# FluxamasynthFeather.net
KiCad netlist of a schematic drawn in EAGLE
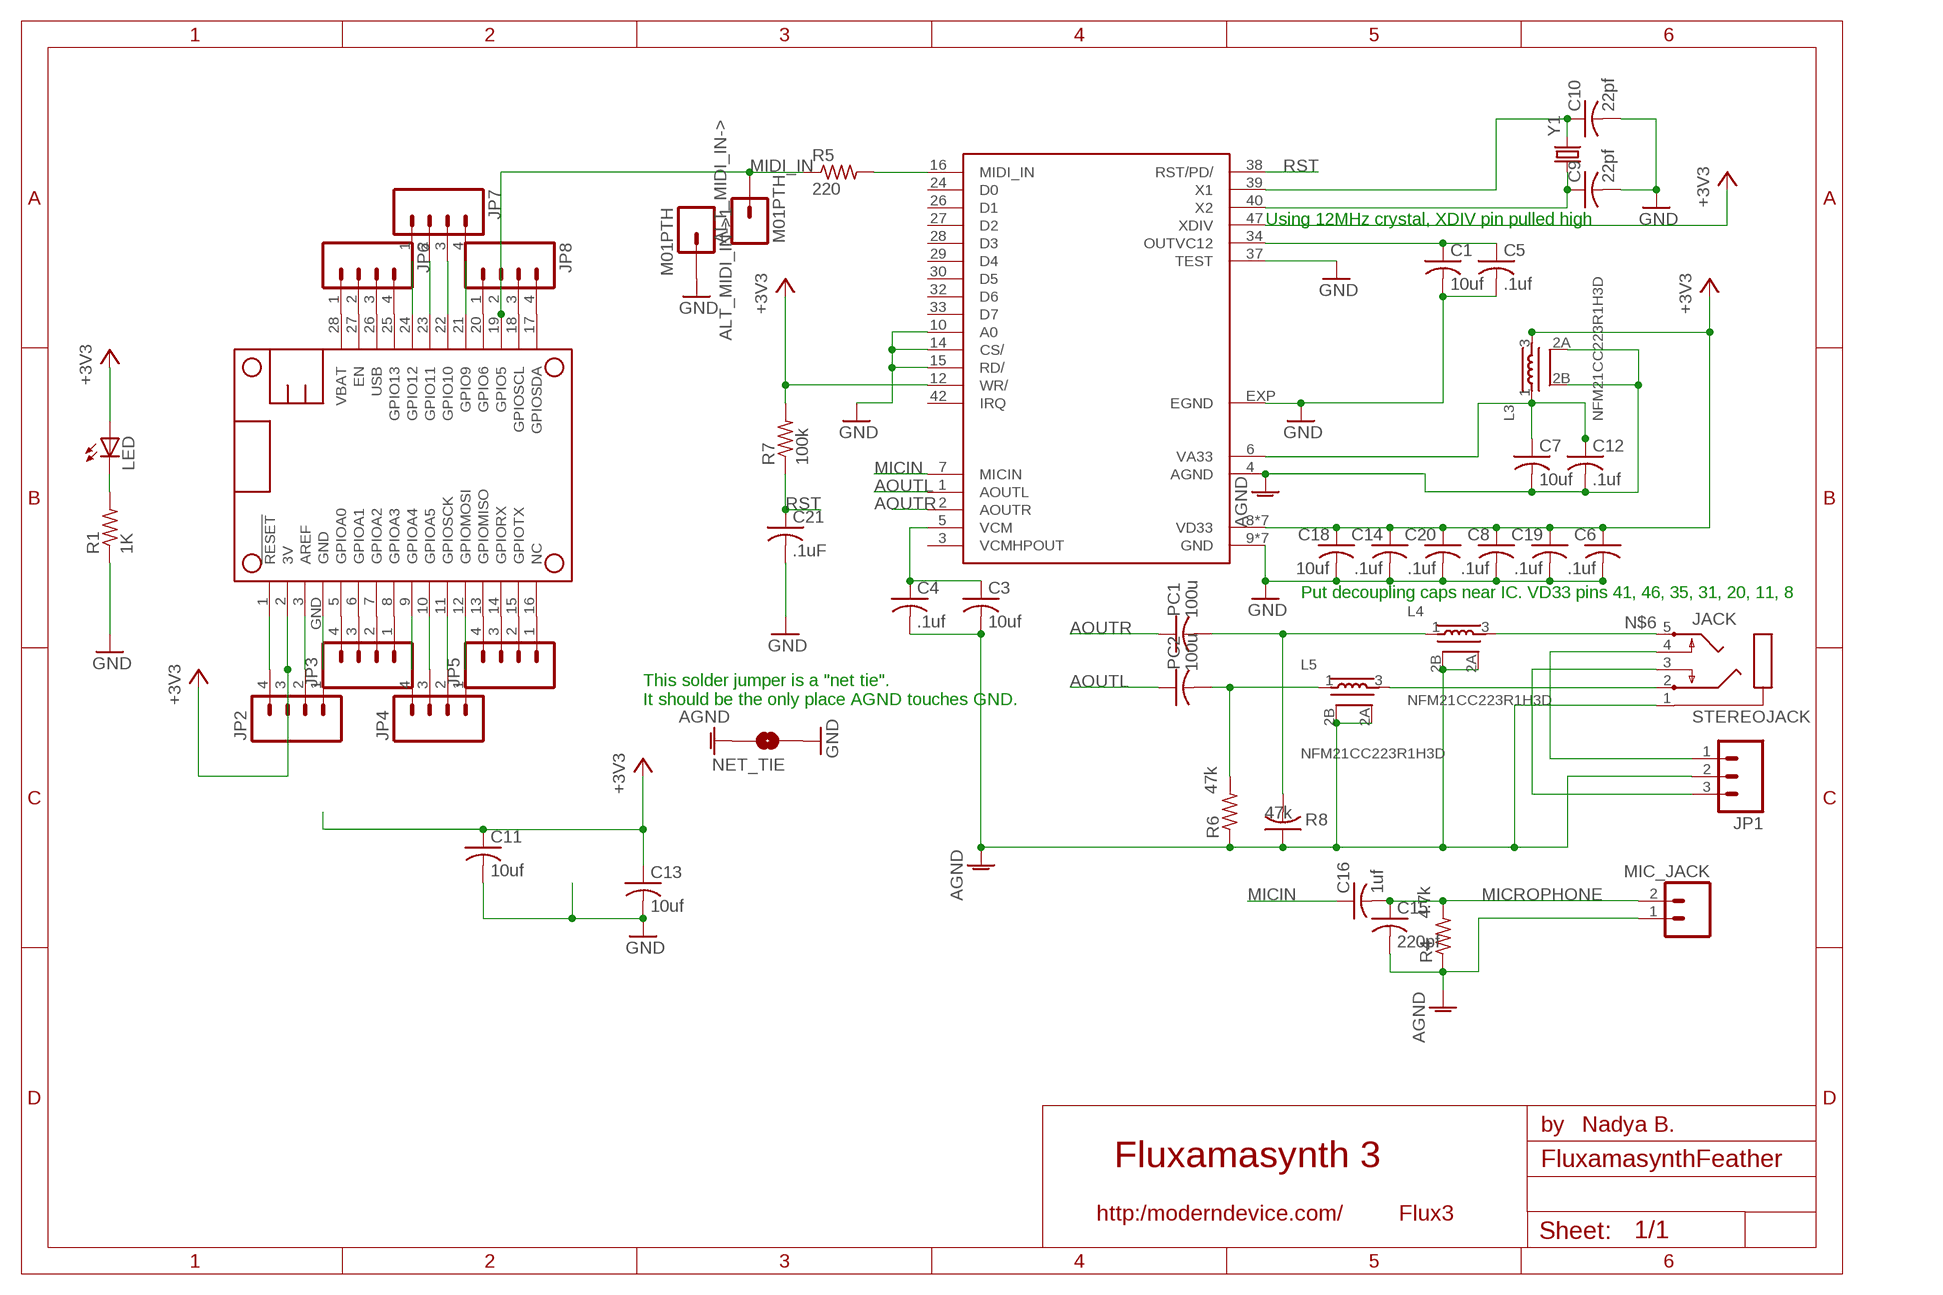
[diagram p0: schematic, sheet 1]

(export (version "E")
  (design (tool "Eeschema 10.0.6"))
  (components
    (comp (ref "ALT_MIDI_IN->")
      (value "M01PTH")
      (footprint "eagle-import:1X01")
      (libsource (lib "eagle-import") (part "M01PTH"))
    )
    (comp (ref "ALT_MIDI_IN->1")
      (value "M01PTH")
      (footprint "eagle-import:1X01")
      (libsource (lib "eagle-import") (part "M01PTH"))
    )
    (comp (ref "C1")
      (value "10uf")
      (footprint "eagle-import:C0805K")
      (libsource (lib "eagle-import") (part "C-USC0805K"))
    )
    (comp (ref "C3")
      (value "10uf")
      (footprint "eagle-import:C0805K")
      (libsource (lib "eagle-import") (part "C-USC0805K"))
    )
    (comp (ref "C4")
      (value ".1uf")
      (footprint "eagle-import:C0603K")
      (libsource (lib "eagle-import") (part "C-USC0603K"))
    )
    (comp (ref "C5")
      (value ".1uf")
      (footprint "eagle-import:C0603K")
      (libsource (lib "eagle-import") (part "C-USC0603K"))
    )
    (comp (ref "C6")
      (value ".1uf")
      (footprint "eagle-import:C0603K")
      (libsource (lib "eagle-import") (part "C-USC0603K"))
    )
    (comp (ref "C7")
      (value "10uf")
      (footprint "eagle-import:C0805K")
      (libsource (lib "eagle-import") (part "C-USC0805K"))
    )
    (comp (ref "C8")
      (value ".1uf")
      (footprint "eagle-import:C0603K")
      (libsource (lib "eagle-import") (part "C-USC0603K"))
    )
    (comp (ref "C9")
      (value "22pf")
      (footprint "eagle-import:C0603")
      (libsource (lib "eagle-import") (part "C-USC0603"))
    )
    (comp (ref "C10")
      (value "22pf")
      (footprint "eagle-import:C0603")
      (libsource (lib "eagle-import") (part "C-USC0603"))
    )
    (comp (ref "C11")
      (value "10uf")
      (footprint "eagle-import:C0805K")
      (libsource (lib "eagle-import") (part "C-USC0805K"))
    )
    (comp (ref "C12")
      (value ".1uf")
      (footprint "eagle-import:C0603K")
      (libsource (lib "eagle-import") (part "C-USC0603K"))
    )
    (comp (ref "C13")
      (value "10uf")
      (footprint "eagle-import:C0805K")
      (libsource (lib "eagle-import") (part "C-USC0805K"))
    )
    (comp (ref "C14")
      (value ".1uf")
      (footprint "eagle-import:C0603K")
      (libsource (lib "eagle-import") (part "C-USC0603K"))
    )
    (comp (ref "C15")
      (value "220pf")
      (footprint "eagle-import:C0805K")
      (libsource (lib "eagle-import") (part "C-USC0805K"))
    )
    (comp (ref "C16")
      (value "1uf")
      (footprint "eagle-import:C0603K")
      (libsource (lib "eagle-import") (part "C-USC0603K"))
    )
    (comp (ref "C18")
      (value "10uf")
      (footprint "eagle-import:C0603K")
      (libsource (lib "eagle-import") (part "C-USC0603K"))
    )
    (comp (ref "C19")
      (value ".1uf")
      (footprint "eagle-import:C0603K")
      (libsource (lib "eagle-import") (part "C-USC0603K"))
    )
    (comp (ref "C20")
      (value ".1uf")
      (footprint "eagle-import:C0603K")
      (libsource (lib "eagle-import") (part "C-USC0603K"))
    )
    (comp (ref "C21")
      (value ".1uF")
      (footprint "eagle-import:C0603K")
      (libsource (lib "eagle-import") (part "C-USC0603K"))
    )
    (comp (ref "JACK")
      (value "STEREOJACK")
      (footprint "eagle-import:STX3100")
      (libsource (lib "eagle-import") (part "STEREOJACK"))
    )
    (comp (ref "JP1")
      (value "M03PTH")
      (footprint "eagle-import:1X03")
      (libsource (lib "eagle-import") (part "M03PTH"))
    )
    (comp (ref "JP2")
      (value "M041X04_NO_SILK")
      (footprint "eagle-import:1X04_NO_SILK")
      (libsource (lib "eagle-import") (part "M041X04_NO_SILK"))
    )
    (comp (ref "JP3")
      (value "M041X04_NO_SILK")
      (footprint "eagle-import:1X04_NO_SILK")
      (libsource (lib "eagle-import") (part "M041X04_NO_SILK"))
    )
    (comp (ref "JP4")
      (value "M041X04_NO_SILK")
      (footprint "eagle-import:1X04_NO_SILK")
      (libsource (lib "eagle-import") (part "M041X04_NO_SILK"))
    )
    (comp (ref "JP5")
      (value "M041X04_NO_SILK")
      (footprint "eagle-import:1X04_NO_SILK")
      (libsource (lib "eagle-import") (part "M041X04_NO_SILK"))
    )
    (comp (ref "JP6")
      (value "M041X04_NO_SILK")
      (footprint "eagle-import:1X04_NO_SILK")
      (libsource (lib "eagle-import") (part "M041X04_NO_SILK"))
    )
    (comp (ref "JP7")
      (value "M041X04_NO_SILK")
      (footprint "eagle-import:1X04_NO_SILK")
      (libsource (lib "eagle-import") (part "M041X04_NO_SILK"))
    )
    (comp (ref "JP8")
      (value "M041X04_NO_SILK")
      (footprint "eagle-import:1X04_NO_SILK")
      (libsource (lib "eagle-import") (part "M041X04_NO_SILK"))
    )
    (comp (ref "L3")
      (value "NFM21CC223R1H3D")
      (footprint "eagle-import:3PC")
      (libsource (lib "eagle-import") (part "NFM21CC223R1H3D"))
    )
    (comp (ref "L4")
      (value "NFM21CC223R1H3D")
      (footprint "eagle-import:3PC")
      (libsource (lib "eagle-import") (part "NFM21CC223R1H3D"))
    )
    (comp (ref "L5")
      (value "NFM21CC223R1H3D")
      (footprint "eagle-import:3PC")
      (libsource (lib "eagle-import") (part "NFM21CC223R1H3D"))
    )
    (comp (ref "LED")
      (value "LED0603")
      (footprint "eagle-import:LED-0603")
      (libsource (lib "eagle-import") (part "LED0603"))
    )
    (comp (ref "MIC_JACK")
      (value "M02PTH")
      (footprint "eagle-import:1X02")
      (libsource (lib "eagle-import") (part "M02PTH"))
    )
    (comp (ref "MS1")
      (value "FEATHERWING")
      (footprint "eagle-import:FEATHERWING")
      (libsource (lib "eagle-import") (part "FEATHERWING"))
    )
    (comp (ref "NET_TIE")
      (value "MODERNDEVICE_SOLDERJUMPERTRACE")
      (footprint "eagle-import:MODERNDEVICE_SJ_2S-TRACE")
      (libsource (lib "eagle-import") (part "MODERNDEVICE_SOLDERJUMPERTRACE"))
    )
    (comp (ref "PC1")
      (value "100u")
      (footprint "eagle-import:C1206K")
      (libsource (lib "eagle-import") (part "C-USC1206K"))
    )
    (comp (ref "PC2")
      (value "100u")
      (footprint "eagle-import:C1206K")
      (libsource (lib "eagle-import") (part "C-USC1206K"))
    )
    (comp (ref "R1")
      (value "1K")
      (footprint "eagle-import:R0603")
      (libsource (lib "eagle-import") (part "R-US_R0603"))
    )
    (comp (ref "R4")
      (value "4.7k")
      (footprint "eagle-import:R0603")
      (libsource (lib "eagle-import") (part "R-US_R0603"))
    )
    (comp (ref "R5")
      (value "220")
      (footprint "eagle-import:R0603")
      (libsource (lib "eagle-import") (part "R-US_R0603"))
    )
    (comp (ref "R6")
      (value "47k")
      (footprint "eagle-import:R0603")
      (libsource (lib "eagle-import") (part "R-US_R0603"))
    )
    (comp (ref "R7")
      (value "100k")
      (footprint "eagle-import:R0603")
      (libsource (lib "eagle-import") (part "R-US_R0603"))
    )
    (comp (ref "R8")
      (value "47k")
      (footprint "eagle-import:C0603K")
      (libsource (lib "eagle-import") (part "C-USC0603K"))
    )
    (comp (ref "SAM2695")
      (value "SAM2695")
      (footprint "eagle-import:QFN48")
      (libsource (lib "eagle-import") (part "SAM2695"))
    )
    (comp (ref "Y1")
      (value "CRYSTALTXC-7A")
      (footprint "eagle-import:CRYSTAL-TXC-7A")
      (libsource (lib "eagle-import") (part "CRYSTALTXC-7A"))
    )
  )
  (nets
    (net (code "1") (name "+3V3") (class "Default")
      (node (ref "C11") (pin "1") (pinfunction "1_1") (pintype "passive"))
      (node (ref "C13") (pin "1") (pinfunction "1_1") (pintype "passive"))
      (node (ref "C14") (pin "1") (pinfunction "1_1") (pintype "passive"))
      (node (ref "C18") (pin "1") (pinfunction "1_1") (pintype "passive"))
      (node (ref "C19") (pin "1") (pinfunction "1_1") (pintype "passive"))
      (node (ref "C20") (pin "1") (pinfunction "1_1") (pintype "passive"))
      (node (ref "C6") (pin "1") (pinfunction "1_1") (pintype "passive"))
      (node (ref "C8") (pin "1") (pinfunction "1_1") (pintype "passive"))
      (node (ref "JP2") (pin "3") (pinfunction "3_3") (pintype "passive"))
      (node (ref "L3") (pin "3") (pinfunction "3_3") (pintype "bidirectional"))
      (node (ref "LED") (pin "A") (pinfunction "A_A") (pintype "passive"))
      (node (ref "MS1") (pin "2") (pinfunction "3V_2") (pintype "power_in"))
      (node (ref "R7") (pin "2") (pinfunction "2_2") (pintype "passive"))
      (node (ref "SAM2695") (pin "11") (pinfunction "VD33_11") (pintype "power_in"))
      (node (ref "SAM2695") (pin "12") (pinfunction "WR/_12") (pintype "input"))
      (node (ref "SAM2695") (pin "20") (pinfunction "VD33_20") (pintype "power_in"))
      (node (ref "SAM2695") (pin "31") (pinfunction "VD33_31") (pintype "power_in"))
      (node (ref "SAM2695") (pin "35") (pinfunction "VD33_35") (pintype "power_in"))
      (node (ref "SAM2695") (pin "41") (pinfunction "VD33_41") (pintype "power_in"))
      (node (ref "SAM2695") (pin "46") (pinfunction "VD33_46") (pintype "power_in"))
      (node (ref "SAM2695") (pin "47") (pinfunction "XDIV_47") (pintype "input"))
      (node (ref "SAM2695") (pin "8") (pinfunction "VD33_8") (pintype "power_in"))
    )
    (net (code "2") (name "/AOUTL") (class "Default")
      (node (ref "PC2") (pin "1") (pinfunction "1_1") (pintype "passive"))
      (node (ref "SAM2695") (pin "1") (pinfunction "AOUTL_1") (pintype "output"))
    )
    (net (code "3") (name "/AOUTR") (class "Default")
      (node (ref "PC1") (pin "1") (pinfunction "1_1") (pintype "passive"))
      (node (ref "SAM2695") (pin "2") (pinfunction "AOUTR_2") (pintype "output"))
    )
    (net (code "4") (name "/MICIN") (class "Default")
      (node (ref "C16") (pin "1") (pinfunction "1_1") (pintype "passive"))
      (node (ref "SAM2695") (pin "7") (pinfunction "MICIN_7") (pintype "input"))
    )
    (net (code "5") (name "/MICROPHONE") (class "Default")
      (node (ref "C15") (pin "1") (pinfunction "1_1") (pintype "passive"))
      (node (ref "C16") (pin "2") (pinfunction "2_2") (pintype "passive"))
      (node (ref "MIC_JACK") (pin "2") (pinfunction "2_2") (pintype "passive"))
      (node (ref "R4") (pin "2") (pinfunction "2_2") (pintype "passive"))
    )
    (net (code "6") (name "/MIDI_IN") (class "Default")
      (node (ref "ALT_MIDI_IN->") (pin "1") (pinfunction "1_1") (pintype "passive"))
      (node (ref "JP8") (pin "2") (pinfunction "2_2") (pintype "passive"))
      (node (ref "MS1") (pin "19") (pinfunction "GPIO5_19") (pintype "bidirectional"))
      (node (ref "R5") (pin "1") (pinfunction "1_1") (pintype "passive"))
    )
    (net (code "7") (name "/N$6") (class "Default")
      (node (ref "JACK") (pin "5") (pinfunction "5_5") (pintype "passive"))
      (node (ref "L4") (pin "3") (pinfunction "3_3") (pintype "bidirectional"))
    )
    (net (code "8") (name "/RST") (class "Default")
      (node (ref "C21") (pin "1") (pinfunction "1_1") (pintype "passive"))
      (node (ref "R7") (pin "1") (pinfunction "1_1") (pintype "passive"))
      (node (ref "SAM2695") (pin "38") (pinfunction "RST/PD/_38") (pintype "input"))
    )
    (net (code "9") (name "AGND") (class "Default")
      (node (ref "C12") (pin "2") (pinfunction "2_2") (pintype "passive"))
      (node (ref "C15") (pin "2") (pinfunction "2_2") (pintype "passive"))
      (node (ref "C3") (pin "2") (pinfunction "2_2") (pintype "passive"))
      (node (ref "C4") (pin "2") (pinfunction "2_2") (pintype "passive"))
      (node (ref "C7") (pin "2") (pinfunction "2_2") (pintype "passive"))
      (node (ref "JACK") (pin "1") (pinfunction "1_1") (pintype "passive"))
      (node (ref "JP1") (pin "2") (pinfunction "2_2") (pintype "passive"))
      (node (ref "L3") (pin "2A") (pinfunction "2A_2A") (pintype "power_in"))
      (node (ref "L3") (pin "2B") (pinfunction "2B_2B") (pintype "power_in"))
      (node (ref "L4") (pin "2A") (pinfunction "2A_2A") (pintype "power_in"))
      (node (ref "L4") (pin "2B") (pinfunction "2B_2B") (pintype "power_in"))
      (node (ref "L5") (pin "2A") (pinfunction "2A_2A") (pintype "power_in"))
      (node (ref "L5") (pin "2B") (pinfunction "2B_2B") (pintype "power_in"))
      (node (ref "MIC_JACK") (pin "1") (pinfunction "1_1") (pintype "passive"))
      (node (ref "NET_TIE") (pin "2") (pinfunction "2_2") (pintype "passive"))
      (node (ref "R4") (pin "1") (pinfunction "1_1") (pintype "passive"))
      (node (ref "R6") (pin "1") (pinfunction "1_1") (pintype "passive"))
      (node (ref "R8") (pin "1") (pinfunction "1_1") (pintype "passive"))
      (node (ref "SAM2695") (pin "4") (pinfunction "AGND_4") (pintype "power_in"))
    )
    (net (code "10") (name "GND") (class "Default")
      (node (ref "ALT_MIDI_IN->1") (pin "1") (pinfunction "1_1") (pintype "passive"))
      (node (ref "C1") (pin "2") (pinfunction "2_2") (pintype "passive"))
      (node (ref "C10") (pin "2") (pinfunction "2_2") (pintype "passive"))
      (node (ref "C11") (pin "2") (pinfunction "2_2") (pintype "passive"))
      (node (ref "C13") (pin "2") (pinfunction "2_2") (pintype "passive"))
      (node (ref "C14") (pin "2") (pinfunction "2_2") (pintype "passive"))
      (node (ref "C18") (pin "2") (pinfunction "2_2") (pintype "passive"))
      (node (ref "C19") (pin "2") (pinfunction "2_2") (pintype "passive"))
      (node (ref "C20") (pin "2") (pinfunction "2_2") (pintype "passive"))
      (node (ref "C21") (pin "2") (pinfunction "2_2") (pintype "passive"))
      (node (ref "C5") (pin "2") (pinfunction "2_2") (pintype "passive"))
      (node (ref "C6") (pin "2") (pinfunction "2_2") (pintype "passive"))
      (node (ref "C8") (pin "2") (pinfunction "2_2") (pintype "passive"))
      (node (ref "C9") (pin "2") (pinfunction "2_2") (pintype "passive"))
      (node (ref "NET_TIE") (pin "1") (pinfunction "1_1") (pintype "passive"))
      (node (ref "R1") (pin "1") (pinfunction "1_1") (pintype "passive"))
      (node (ref "SAM2695") (pin "10") (pinfunction "A0_10") (pintype "input"))
      (node (ref "SAM2695") (pin "13") (pinfunction "GND_13") (pintype "power_in"))
      (node (ref "SAM2695") (pin "14") (pinfunction "CS/_14") (pintype "input"))
      (node (ref "SAM2695") (pin "15") (pinfunction "RD/_15") (pintype "input"))
      (node (ref "SAM2695") (pin "18") (pinfunction "GND_18") (pintype "power_in"))
      (node (ref "SAM2695") (pin "25") (pinfunction "GND_25") (pintype "power_in"))
      (node (ref "SAM2695") (pin "36") (pinfunction "GND_36") (pintype "power_in"))
      (node (ref "SAM2695") (pin "37") (pinfunction "TEST_37") (pintype "input"))
      (node (ref "SAM2695") (pin "45") (pinfunction "GND_45") (pintype "power_in"))
      (node (ref "SAM2695") (pin "48") (pinfunction "GND_48") (pintype "power_in"))
      (node (ref "SAM2695") (pin "9") (pinfunction "GND_9") (pintype "power_in"))
      (node (ref "SAM2695") (pin "EXP") (pinfunction "EGND_EXP") (pintype "power_in"))
    )
    (net (code "11") (name "Net-(JACK-Pad2)") (class "Default")
      (node (ref "JACK") (pin "2") (pinfunction "2_2") (pintype "passive"))
      (node (ref "L5") (pin "3") (pinfunction "3_3") (pintype "bidirectional"))
    )
    (net (code "12") (name "Net-(JACK-Pad3)") (class "Default")
      (node (ref "JACK") (pin "3") (pinfunction "3_3") (pintype "passive"))
      (node (ref "JP1") (pin "3") (pinfunction "3_3") (pintype "passive"))
    )
    (net (code "13") (name "Net-(JACK-Pad4)") (class "Default")
      (node (ref "JACK") (pin "4") (pinfunction "4_4") (pintype "passive"))
      (node (ref "JP1") (pin "1") (pinfunction "1_1") (pintype "passive"))
    )
    (net (code "14") (name "Net-(JP2-Pad1)") (class "Default")
      (node (ref "JP2") (pin "1") (pinfunction "1_1") (pintype "passive"))
      (node (ref "MS1") (pin "GND") (pinfunction "GND_GND") (pintype "power_in"))
    )
    (net (code "15") (name "Net-(L4-Pad1)") (class "Default")
      (node (ref "L4") (pin "1") (pinfunction "1_1") (pintype "bidirectional"))
      (node (ref "PC1") (pin "2") (pinfunction "2_2") (pintype "passive"))
      (node (ref "R8") (pin "2") (pinfunction "2_2") (pintype "passive"))
    )
    (net (code "16") (name "Net-(L5-Pad1)") (class "Default")
      (node (ref "L5") (pin "1") (pinfunction "1_1") (pintype "bidirectional"))
      (node (ref "PC2") (pin "2") (pinfunction "2_2") (pintype "passive"))
      (node (ref "R6") (pin "2") (pinfunction "2_2") (pintype "passive"))
    )
    (net (code "17") (name "Net-(LED-PadC)") (class "Default")
      (node (ref "LED") (pin "C") (pinfunction "C_C") (pintype "passive"))
      (node (ref "R1") (pin "2") (pinfunction "2_2") (pintype "passive"))
    )
    (net (code "18") (name "Net-(MS1-AREF)") (class "Default")
      (node (ref "JP2") (pin "2") (pinfunction "2_2") (pintype "passive"))
      (node (ref "MS1") (pin "3") (pinfunction "AREF_3") (pintype "passive"))
    )
    (net (code "19") (name "Net-(MS1-EN)") (class "Default")
      (node (ref "JP6") (pin "2") (pinfunction "2_2") (pintype "passive"))
      (node (ref "MS1") (pin "27") (pinfunction "EN_27") (pintype "passive"))
    )
    (net (code "20") (name "Net-(MS1-GPIO6)") (class "Default")
      (node (ref "JP8") (pin "1") (pinfunction "1_1") (pintype "passive"))
      (node (ref "MS1") (pin "20") (pinfunction "GPIO6_20") (pintype "bidirectional"))
    )
    (net (code "21") (name "Net-(MS1-GPIO9)") (class "Default")
      (node (ref "JP7") (pin "4") (pinfunction "4_4") (pintype "passive"))
      (node (ref "MS1") (pin "21") (pinfunction "GPIO9_21") (pintype "bidirectional"))
    )
    (net (code "22") (name "Net-(MS1-GPIO10)") (class "Default")
      (node (ref "JP7") (pin "3") (pinfunction "3_3") (pintype "passive"))
      (node (ref "MS1") (pin "22") (pinfunction "GPIO10_22") (pintype "bidirectional"))
    )
    (net (code "23") (name "Net-(MS1-GPIO11)") (class "Default")
      (node (ref "JP7") (pin "2") (pinfunction "2_2") (pintype "passive"))
      (node (ref "MS1") (pin "23") (pinfunction "GPIO11_23") (pintype "bidirectional"))
    )
    (net (code "24") (name "Net-(MS1-GPIO12)") (class "Default")
      (node (ref "JP7") (pin "1") (pinfunction "1_1") (pintype "passive"))
      (node (ref "MS1") (pin "24") (pinfunction "GPIO12_24") (pintype "bidirectional"))
    )
    (net (code "25") (name "Net-(MS1-GPIO13)") (class "Default")
      (node (ref "JP6") (pin "4") (pinfunction "4_4") (pintype "passive"))
      (node (ref "MS1") (pin "25") (pinfunction "GPIO13_25") (pintype "bidirectional"))
    )
    (net (code "26") (name "Net-(MS1-GPIOA0)") (class "Default")
      (node (ref "JP3") (pin "4") (pinfunction "4_4") (pintype "passive"))
      (node (ref "MS1") (pin "5") (pinfunction "GPIOA0_5") (pintype "bidirectional"))
    )
    (net (code "27") (name "Net-(MS1-GPIOA1)") (class "Default")
      (node (ref "JP3") (pin "3") (pinfunction "3_3") (pintype "passive"))
      (node (ref "MS1") (pin "6") (pinfunction "GPIOA1_6") (pintype "bidirectional"))
    )
    (net (code "28") (name "Net-(MS1-GPIOA2)") (class "Default")
      (node (ref "JP3") (pin "2") (pinfunction "2_2") (pintype "passive"))
      (node (ref "MS1") (pin "7") (pinfunction "GPIOA2_7") (pintype "bidirectional"))
    )
    (net (code "29") (name "Net-(MS1-GPIOA3)") (class "Default")
      (node (ref "JP3") (pin "1") (pinfunction "1_1") (pintype "passive"))
      (node (ref "MS1") (pin "8") (pinfunction "GPIOA3_8") (pintype "bidirectional"))
    )
    (net (code "30") (name "Net-(MS1-GPIOA4)") (class "Default")
      (node (ref "JP4") (pin "4") (pinfunction "4_4") (pintype "passive"))
      (node (ref "MS1") (pin "9") (pinfunction "GPIOA4_9") (pintype "bidirectional"))
    )
    (net (code "31") (name "Net-(MS1-GPIOA5)") (class "Default")
      (node (ref "JP4") (pin "3") (pinfunction "3_3") (pintype "passive"))
      (node (ref "MS1") (pin "10") (pinfunction "GPIOA5_10") (pintype "bidirectional"))
    )
    (net (code "32") (name "Net-(MS1-GPIOMISO)") (class "Default")
      (node (ref "JP5") (pin "4") (pinfunction "4_4") (pintype "passive"))
      (node (ref "MS1") (pin "13") (pinfunction "GPIOMISO_13") (pintype "bidirectional"))
    )
    (net (code "33") (name "Net-(MS1-GPIOMOSI)") (class "Default")
      (node (ref "JP4") (pin "1") (pinfunction "1_1") (pintype "passive"))
      (node (ref "MS1") (pin "12") (pinfunction "GPIOMOSI_12") (pintype "bidirectional"))
    )
    (net (code "34") (name "Net-(MS1-GPIORX)") (class "Default")
      (node (ref "JP5") (pin "3") (pinfunction "3_3") (pintype "passive"))
      (node (ref "MS1") (pin "14") (pinfunction "GPIORX_14") (pintype "bidirectional"))
    )
    (net (code "35") (name "Net-(MS1-GPIOSCK)") (class "Default")
      (node (ref "JP4") (pin "2") (pinfunction "2_2") (pintype "passive"))
      (node (ref "MS1") (pin "11") (pinfunction "GPIOSCK_11") (pintype "bidirectional"))
    )
    (net (code "36") (name "Net-(MS1-GPIOSCL)") (class "Default")
      (node (ref "JP8") (pin "3") (pinfunction "3_3") (pintype "passive"))
      (node (ref "MS1") (pin "18") (pinfunction "GPIOSCL_18") (pintype "bidirectional"))
    )
    (net (code "37") (name "Net-(MS1-GPIOSDA)") (class "Default")
      (node (ref "JP8") (pin "4") (pinfunction "4_4") (pintype "passive"))
      (node (ref "MS1") (pin "17") (pinfunction "GPIOSDA_17") (pintype "bidirectional"))
    )
    (net (code "38") (name "Net-(MS1-GPIOTX)") (class "Default")
      (node (ref "JP5") (pin "2") (pinfunction "2_2") (pintype "passive"))
      (node (ref "MS1") (pin "15") (pinfunction "GPIOTX_15") (pintype "bidirectional"))
    )
    (net (code "39") (name "Net-(MS1-NC)") (class "Default")
      (node (ref "JP5") (pin "1") (pinfunction "1_1") (pintype "passive"))
      (node (ref "MS1") (pin "16") (pinfunction "NC_16") (pintype "passive"))
    )
    (net (code "40") (name "Net-(MS1-USB)") (class "Default")
      (node (ref "JP6") (pin "3") (pinfunction "3_3") (pintype "passive"))
      (node (ref "MS1") (pin "26") (pinfunction "USB_26") (pintype "power_in"))
    )
    (net (code "41") (name "Net-(MS1-VBAT)") (class "Default")
      (node (ref "JP6") (pin "1") (pinfunction "1_1") (pintype "passive"))
      (node (ref "MS1") (pin "28") (pinfunction "VBAT_28") (pintype "power_in"))
    )
    (net (code "42") (name "Net-(MS1-~{RESET})") (class "Default")
      (node (ref "JP2") (pin "4") (pinfunction "4_4") (pintype "passive"))
      (node (ref "MS1") (pin "1") (pinfunction "~{RESET}_1") (pintype "input"))
    )
    (net (code "43") (name "Net-(SAM2695-MIDI_IN)") (class "Default")
      (node (ref "R5") (pin "2") (pinfunction "2_2") (pintype "passive"))
      (node (ref "SAM2695") (pin "16") (pinfunction "MIDI_IN_16") (pintype "input"))
    )
    (net (code "44") (name "Net-(SAM2695-OUTVC12)") (class "Default")
      (node (ref "C1") (pin "1") (pinfunction "1_1") (pintype "passive"))
      (node (ref "C5") (pin "1") (pinfunction "1_1") (pintype "passive"))
      (node (ref "SAM2695") (pin "34") (pinfunction "OUTVC12_34") (pintype "power_in"))
    )
    (net (code "45") (name "Net-(SAM2695-VA33)") (class "Default")
      (node (ref "C12") (pin "1") (pinfunction "1_1") (pintype "passive"))
      (node (ref "C7") (pin "1") (pinfunction "1_1") (pintype "passive"))
      (node (ref "L3") (pin "1") (pinfunction "1_1") (pintype "bidirectional"))
      (node (ref "SAM2695") (pin "6") (pinfunction "VA33_6") (pintype "power_in"))
    )
    (net (code "46") (name "Net-(SAM2695-VCM)") (class "Default")
      (node (ref "C3") (pin "1") (pinfunction "1_1") (pintype "passive"))
      (node (ref "C4") (pin "1") (pinfunction "1_1") (pintype "passive"))
      (node (ref "SAM2695") (pin "5") (pinfunction "VCM_5") (pintype "output"))
    )
    (net (code "47") (name "Net-(SAM2695-X1)") (class "Default")
      (node (ref "C10") (pin "1") (pinfunction "1_1") (pintype "passive"))
      (node (ref "SAM2695") (pin "39") (pinfunction "X1_39") (pintype "bidirectional"))
      (node (ref "Y1") (pin "P$2") (pinfunction "2_P$2") (pintype "passive"))
    )
    (net (code "48") (name "Net-(SAM2695-X2)") (class "Default")
      (node (ref "C9") (pin "1") (pinfunction "1_1") (pintype "passive"))
      (node (ref "SAM2695") (pin "40") (pinfunction "X2_40") (pintype "bidirectional"))
      (node (ref "Y1") (pin "P$1") (pinfunction "1_P$1") (pintype "passive"))
    )
    (net (code "49") (name "unconnected-(SAM2695-D0-Pad24)") (class "Default")
      (node (ref "SAM2695") (pin "24") (pinfunction "D0_24") (pintype "bidirectional"))
    )
    (net (code "50") (name "unconnected-(SAM2695-D1-Pad26)") (class "Default")
      (node (ref "SAM2695") (pin "26") (pinfunction "D1_26") (pintype "bidirectional"))
    )
    (net (code "51") (name "unconnected-(SAM2695-D2-Pad27)") (class "Default")
      (node (ref "SAM2695") (pin "27") (pinfunction "D2_27") (pintype "bidirectional"))
    )
    (net (code "52") (name "unconnected-(SAM2695-D3-Pad28)") (class "Default")
      (node (ref "SAM2695") (pin "28") (pinfunction "D3_28") (pintype "bidirectional"))
    )
    (net (code "53") (name "unconnected-(SAM2695-D4-Pad29)") (class "Default")
      (node (ref "SAM2695") (pin "29") (pinfunction "D4_29") (pintype "bidirectional"))
    )
    (net (code "54") (name "unconnected-(SAM2695-D5-Pad30)") (class "Default")
      (node (ref "SAM2695") (pin "30") (pinfunction "D5_30") (pintype "bidirectional"))
    )
    (net (code "55") (name "unconnected-(SAM2695-D6-Pad32)") (class "Default")
      (node (ref "SAM2695") (pin "32") (pinfunction "D6_32") (pintype "bidirectional"))
    )
    (net (code "56") (name "unconnected-(SAM2695-D7-Pad33)") (class "Default")
      (node (ref "SAM2695") (pin "33") (pinfunction "D7_33") (pintype "bidirectional"))
    )
    (net (code "57") (name "unconnected-(SAM2695-IRQ-Pad42)") (class "Default")
      (node (ref "SAM2695") (pin "42") (pinfunction "IRQ_42") (pintype "output"))
    )
    (net (code "58") (name "unconnected-(SAM2695-VCMHPOUT-Pad3)") (class "Default")
      (node (ref "SAM2695") (pin "3") (pinfunction "VCMHPOUT_3") (pintype "output"))
    )
  )
)
